# power.net
KiCad netlist of a schematic drawn in Altium Designer
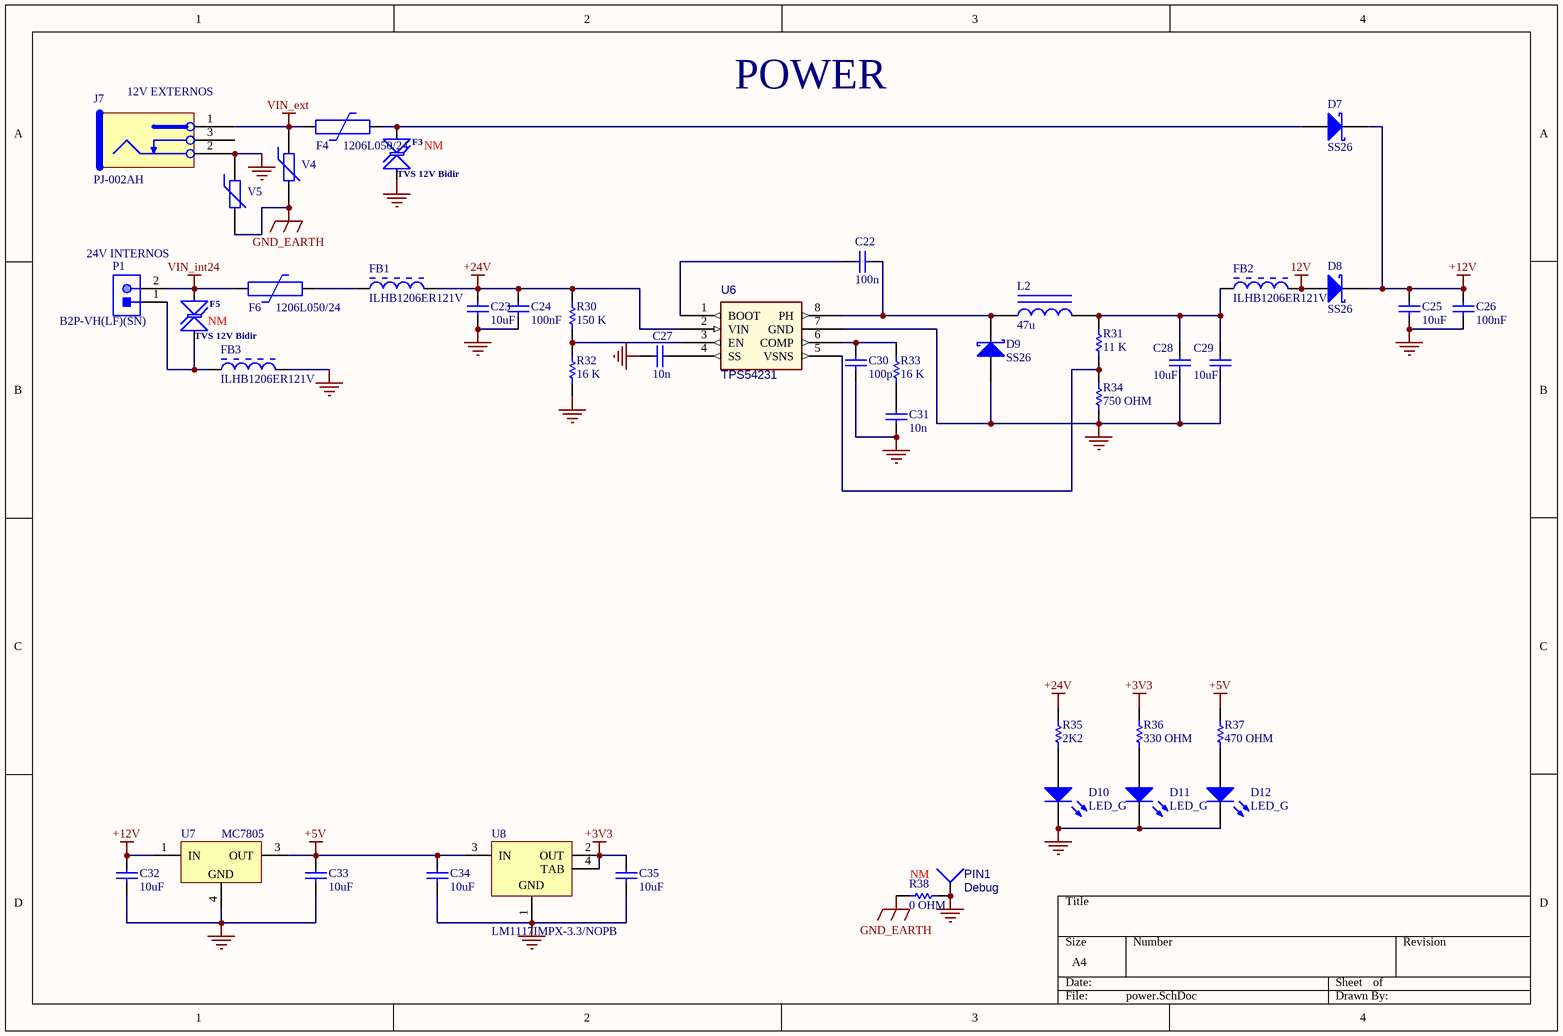
[diagram p0: power.SchDoc]

(export (version "E")
  (design (tool "Eeschema 10.0.6"))
  (components
    (comp (ref "C22")
      (value "100n")
      (footprint "0603")
      (description "Capacitor")
      (fields (field (name "PUBLISHER") "Altium Limited"))
      (libsource (lib "sallen") (part "cond"))
    )
    (comp (ref "C23")
      (value "10uF")
      (footprint "1206")
      (description "Capacitor")
      (fields (field (name "PUBLISHER") "Altium Limited"))
      (libsource (lib "sallen") (part "cond"))
    )
    (comp (ref "C24")
      (value "100nF")
      (footprint "0805")
      (description "Capacitor")
      (fields (field (name "PUBLISHER") "Altium Limited"))
      (libsource (lib "sallen") (part "cond"))
    )
    (comp (ref "C25")
      (value "10uF")
      (footprint "1206")
      (description "Capacitor")
      (fields (field (name "PUBLISHER") "Altium Limited"))
      (libsource (lib "sallen") (part "cond"))
    )
    (comp (ref "C26")
      (value "100nF")
      (footprint "0805")
      (description "Capacitor")
      (fields (field (name "PUBLISHER") "Altium Limited"))
      (libsource (lib "sallen") (part "cond"))
    )
    (comp (ref "C27")
      (value "10n")
      (footprint "0603")
      (description "Capacitor")
      (fields (field (name "PUBLISHER") "Altium Limited"))
      (libsource (lib "sallen") (part "cond"))
    )
    (comp (ref "C28")
      (value "10uF")
      (footprint "1206")
      (description "Capacitor")
      (fields (field (name "PUBLISHER") "Altium Limited"))
      (libsource (lib "sallen") (part "cond"))
    )
    (comp (ref "C29")
      (value "10uF")
      (footprint "1206")
      (description "Capacitor")
      (fields (field (name "PUBLISHER") "Altium Limited"))
      (libsource (lib "sallen") (part "cond"))
    )
    (comp (ref "C30")
      (value "100p")
      (footprint "0603")
      (description "Capacitor")
      (fields (field (name "PUBLISHER") "Altium Limited"))
      (libsource (lib "sallen") (part "cond"))
    )
    (comp (ref "C31")
      (value "10n")
      (footprint "0603")
      (description "Capacitor")
      (fields (field (name "PUBLISHER") "Altium Limited"))
      (libsource (lib "sallen") (part "cond"))
    )
    (comp (ref "C32")
      (value "10uF")
      (footprint "1206")
      (description "Capacitor")
      (fields (field (name "PUBLISHER") "Altium Limited"))
      (libsource (lib "sallen") (part "cond"))
    )
    (comp (ref "C33")
      (value "10uF")
      (footprint "0805")
      (description "Capacitor")
      (fields (field (name "PUBLISHER") "Altium Limited"))
      (libsource (lib "sallen") (part "cond"))
    )
    (comp (ref "C34")
      (value "10uF")
      (footprint "1206")
      (description "Capacitor")
      (fields (field (name "PUBLISHER") "Altium Limited"))
      (libsource (lib "sallen") (part "cond"))
    )
    (comp (ref "C35")
      (value "10uF")
      (footprint "0805")
      (description "Capacitor")
      (fields (field (name "PUBLISHER") "Altium Limited"))
      (libsource (lib "sallen") (part "cond"))
    )
    (comp (ref "D7")
      (value "SS26")
      (footprint "SMB")
      (description "Schottky Diode")
      (fields (field (name "PUBLISHER") "Altium Limited"))
      (libsource (lib "sallen") (part "D Schottky"))
    )
    (comp (ref "D8")
      (value "SS26")
      (footprint "SMB")
      (description "Schottky Diode")
      (fields (field (name "PUBLISHER") "Altium Limited"))
      (libsource (lib "sallen") (part "D Schottky"))
    )
    (comp (ref "D9")
      (value "SS26")
      (footprint "SMB")
      (description "Schottky Diode")
      (fields (field (name "PUBLISHER") "Altium Limited"))
      (libsource (lib "sallen") (part "D Schottky"))
    )
    (comp (ref "D10")
      (value "LED_G")
      (footprint "LED0603G")
      (description "Typical RED, GREEN, YELLOW, AMBER GaAs LED")
      (fields (field (name "PUBLISHER") "Altium Limited"))
      (libsource (lib "sallen") (part "diodo_led"))
    )
    (comp (ref "D11")
      (value "LED_G")
      (footprint "LED0603G")
      (description "Typical RED, GREEN, YELLOW, AMBER GaAs LED")
      (fields (field (name "PUBLISHER") "Altium Limited"))
      (libsource (lib "sallen") (part "diodo_led"))
    )
    (comp (ref "D12")
      (value "LED_G")
      (footprint "LED0603G")
      (description "Typical RED, GREEN, YELLOW, AMBER GaAs LED")
      (fields (field (name "PUBLISHER") "Altium Limited"))
      (libsource (lib "sallen") (part "diodo_led"))
    )
    (comp (ref "F3")
      (value "TVS 12V Bidir")
      (footprint "DO-214AA")
      (description "TVS 12V 600W Bidir SMD")
      (libsource (lib "HSDS_2.0") (part "SMBJ12CA"))
    )
    (comp (ref "F4")
      (value "1206L050/24")
      (footprint "POLYFUSE_1206L")
      (libsource (lib "dpm_semiconductores") (part "POLYFUSE_1206L050/24"))
    )
    (comp (ref "F5")
      (value "TVS 12V Bidir")
      (footprint "DO-214AA")
      (description "TVS 12V 600W Bidir SMD")
      (libsource (lib "HSDS_2.0") (part "SMBJ12CA"))
    )
    (comp (ref "F6")
      (value "1206L050/24")
      (footprint "POLYFUSE_1206L")
      (libsource (lib "dpm_semiconductores") (part "POLYFUSE_1206L050/24"))
    )
    (comp (ref "FB1") (value "ILHB1206ER121V") (footprint "1206") (libsource (lib "sallen") (part "FERRITA")))
    (comp (ref "FB2") (value "ILHB1206ER121V") (footprint "1206") (libsource (lib "sallen") (part "FERRITA")))
    (comp (ref "FB3") (value "ILHB1206ER121V") (footprint "1206") (libsource (lib "sallen") (part "FERRITA")))
    (comp (ref "J7")
      (value "PJ-002AH")
      (footprint "POWER_JACK_5.5_2.1MM_NS_v1.1")
      (description "CONN PWR JACK 2.1X5.5MM HIGH CUR")
      (fields
        (field (name "MANUFACTURER") "CUI Inc")
        (field (name ".CHECKED PCB") "MM")
        (field (name ".CHECKED SCH") "MM")
        (field (name ".CREATOR") "MM")
      )
      (libsource (lib "OpenRex_V1I1") (part "PJ-002AH_v1.1"))
    )
    (comp (ref "L2")
      (value "47u")
      (footprint "SRU1048-470Y")
      (description "SRU1048-470Y")
      (libsource (lib "dpm_pasivos") (part "SRU1048-470Y"))
    )
    (comp (ref "P1")
      (value "B2P-VH(LF)(SN)")
      (footprint "JST-B2P-VH(LF)(SN)_V")
      (fields (field (name "TOLERANCE") "5%"))
      (libsource (lib "sallen") (part "B2P-VH(LF)(SN)"))
    )
    (comp (ref "PIN1")
      (value "Debug")
      (description "PIN DE NET PUNTUAL /Pin Strip")
      (libsource (lib "LMB_Board") (part "Pin_Debug"))
    )
    (comp (ref "R30")
      (value "150 K")
      (footprint "R0603")
      (description "Resistor")
      (fields (field (name "PUBLISHER") "Altium Limited"))
      (libsource (lib "sallen") (part "res1"))
    )
    (comp (ref "R31")
      (value "11 K")
      (footprint "R0603")
      (description "Resistor")
      (fields (field (name "PUBLISHER") "Altium Limited"))
      (libsource (lib "sallen") (part "res1"))
    )
    (comp (ref "R32")
      (value "16 K")
      (footprint "R0603")
      (description "Resistor")
      (fields (field (name "PUBLISHER") "Altium Limited"))
      (libsource (lib "sallen") (part "res1"))
    )
    (comp (ref "R33")
      (value "16 K")
      (footprint "R0603")
      (description "Resistor")
      (fields (field (name "PUBLISHER") "Altium Limited"))
      (libsource (lib "sallen") (part "res1"))
    )
    (comp (ref "R34")
      (value "750 OHM")
      (footprint "R0603")
      (description "Resistor")
      (fields (field (name "PUBLISHER") "Altium Limited"))
      (libsource (lib "sallen") (part "res1"))
    )
    (comp (ref "R35")
      (value "2K2")
      (footprint "R0603")
      (description "Resistor")
      (fields (field (name "PUBLISHER") "Altium Limited"))
      (libsource (lib "sallen") (part "res1"))
    )
    (comp (ref "R36")
      (value "330 OHM")
      (footprint "R0603")
      (description "Resistor")
      (fields (field (name "PUBLISHER") "Altium Limited"))
      (libsource (lib "sallen") (part "res1"))
    )
    (comp (ref "R37")
      (value "470 OHM")
      (footprint "R0603")
      (description "Resistor")
      (fields (field (name "PUBLISHER") "Altium Limited"))
      (libsource (lib "sallen") (part "res1"))
    )
    (comp (ref "R38")
      (value "0 OHM")
      (footprint "R1206")
      (description "Resistor")
      (fields (field (name "PUBLISHER") "Altium Limited"))
      (libsource (lib "sallen") (part "res1"))
    )
    (comp (ref "U6")
      (value "TPS54231")
      (description "2A, 28V INPUT, STEP DOWN SWIFT™ DC/DC CONVERTER WITH ECO-MODE")
      (fields (field (name "PART NUMBER") "TEXAS TPS54231D") (field (name "PROVIDER") "ISEE"))
      (libsource (lib "LMB_Board") (part "TPS54231"))
    )
    (comp (ref "U7") (value "MC7805") (footprint "D2PAK") (libsource (lib "sallen") (part "MC7805")))
    (comp (ref "U8")
      (value "LM1117IMPX-3.3/NOPB")
      (footprint "SOT223_")
      (description "800mA Low-Dropout Linear Regulator, 4-pin SOT-223, Pb-Free")
      (fields (field (name "MANUFACTURER") "National Semiconductor"))
      (libsource (lib "sallen") (part "LM1117IMPX-3.3/NOPB"))
    )
    (comp (ref "V4")
      (value "VC080526C580")
      (footprint "VC080526C580")
      (description "Varistor (Voltage-Sensitive Resistor)")
      (libsource (lib "dpm_pasivos") (part "VC080526C580"))
    )
    (comp (ref "V5")
      (value "VC080526C580")
      (footprint "VC080526C580")
      (description "Varistor (Voltage-Sensitive Resistor)")
      (libsource (lib "dpm_pasivos") (part "VC080526C580"))
    )
  )
  (nets
    (net (code "1") (name "+3V3") (class "Default")
      (node (ref "C35") (pin "2") (pinfunction "2_2") (pintype "passive"))
      (node (ref "R36") (pin "2") (pinfunction "2_2") (pintype "passive"))
      (node (ref "U8") (pin "2") (pinfunction "OUT_2") (pintype "power_in"))
      (node (ref "U8") (pin "4") (pinfunction "TAB_4") (pintype "power_in"))
    )
    (net (code "2") (name "+5V") (class "Default")
      (node (ref "C33") (pin "2") (pinfunction "2_2") (pintype "passive"))
      (node (ref "C34") (pin "2") (pinfunction "2_2") (pintype "passive"))
      (node (ref "R37") (pin "2") (pinfunction "2_2") (pintype "passive"))
      (node (ref "U7") (pin "3") (pinfunction "OUT_3") (pintype "power_in"))
      (node (ref "U8") (pin "3") (pinfunction "IN_3") (pintype "power_in"))
    )
    (net (code "3") (name "+12V") (class "Default")
      (node (ref "C25") (pin "1") (pinfunction "1_1") (pintype "passive"))
      (node (ref "C26") (pin "2") (pinfunction "2_2") (pintype "passive"))
      (node (ref "C32") (pin "2") (pinfunction "2_2") (pintype "passive"))
      (node (ref "D7") (pin "2") (pinfunction "K_2") (pintype "passive"))
      (node (ref "D8") (pin "2") (pinfunction "K_2") (pintype "passive"))
      (node (ref "U7") (pin "1") (pinfunction "IN_1") (pintype "power_in"))
    )
    (net (code "4") (name "+24V") (class "Default")
      (node (ref "C23") (pin "2") (pinfunction "2_2") (pintype "passive"))
      (node (ref "C24") (pin "2") (pinfunction "2_2") (pintype "passive"))
      (node (ref "FB1") (pin "2") (pinfunction "2_2") (pintype "passive"))
      (node (ref "R30") (pin "2") (pinfunction "2_2") (pintype "passive"))
      (node (ref "R35") (pin "2") (pinfunction "2_2") (pintype "passive"))
      (node (ref "U6") (pin "2") (pinfunction "VIN_2") (pintype "input"))
    )
    (net (code "5") (name "12V") (class "Default")
      (node (ref "D8") (pin "1") (pinfunction "A_1") (pintype "passive"))
      (node (ref "FB2") (pin "2") (pinfunction "2_2") (pintype "passive"))
    )
    (net (code "6") (name "GND") (class "Default")
      (node (ref "C23") (pin "1") (pinfunction "1_1") (pintype "passive"))
      (node (ref "C24") (pin "1") (pinfunction "1_1") (pintype "passive"))
      (node (ref "C25") (pin "2") (pinfunction "2_2") (pintype "passive"))
      (node (ref "C26") (pin "1") (pinfunction "1_1") (pintype "passive"))
      (node (ref "C27") (pin "2") (pinfunction "2_2") (pintype "passive"))
      (node (ref "C28") (pin "1") (pinfunction "1_1") (pintype "passive"))
      (node (ref "C29") (pin "1") (pinfunction "1_1") (pintype "passive"))
      (node (ref "C30") (pin "1") (pinfunction "1_1") (pintype "passive"))
      (node (ref "C31") (pin "1") (pinfunction "1_1") (pintype "passive"))
      (node (ref "C32") (pin "1") (pinfunction "1_1") (pintype "passive"))
      (node (ref "C33") (pin "1") (pinfunction "1_1") (pintype "passive"))
      (node (ref "C34") (pin "1") (pinfunction "1_1") (pintype "passive"))
      (node (ref "C35") (pin "1") (pinfunction "1_1") (pintype "passive"))
      (node (ref "D10") (pin "2") (pinfunction "K_2") (pintype "passive"))
      (node (ref "D11") (pin "2") (pinfunction "K_2") (pintype "passive"))
      (node (ref "D12") (pin "2") (pinfunction "K_2") (pintype "passive"))
      (node (ref "D9") (pin "1") (pinfunction "A_1") (pintype "passive"))
      (node (ref "F3") (pin "1") (pinfunction "A_1") (pintype "passive"))
      (node (ref "FB3") (pin "2") (pinfunction "2_2") (pintype "passive"))
      (node (ref "J7") (pin "2") (pinfunction "2_2") (pintype "passive"))
      (node (ref "PIN1") (pin "1") (pinfunction "1_1") (pintype "passive"))
      (node (ref "R32") (pin "1") (pinfunction "1_1") (pintype "passive"))
      (node (ref "R34") (pin "1") (pinfunction "1_1") (pintype "passive"))
      (node (ref "R38") (pin "2") (pinfunction "2_2") (pintype "passive"))
      (node (ref "U6") (pin "7") (pinfunction "GND_7") (pintype "passive"))
      (node (ref "U7") (pin "4") (pinfunction "GND_4") (pintype "power_in"))
      (node (ref "U8") (pin "1") (pinfunction "GND_1") (pintype "power_in"))
      (node (ref "V5") (pin "1") (pinfunction "1_1") (pintype "passive"))
    )
    (net (code "7") (name "GND_EARTH") (class "Default")
      (node (ref "R38") (pin "1") (pinfunction "1_1") (pintype "passive"))
      (node (ref "V4") (pin "2") (pinfunction "2_2") (pintype "passive"))
      (node (ref "V5") (pin "2") (pinfunction "2_2") (pintype "passive"))
    )
    (net (code "8") (name "Net-(C28-Pad2)") (class "Default")
      (node (ref "C28") (pin "2") (pinfunction "2_2") (pintype "passive"))
      (node (ref "C29") (pin "2") (pinfunction "2_2") (pintype "passive"))
      (node (ref "FB2") (pin "1") (pinfunction "1_1") (pintype "passive"))
      (node (ref "L2") (pin "2") (pinfunction "2_2") (pintype "passive"))
      (node (ref "R31") (pin "2") (pinfunction "2_2") (pintype "passive"))
    )
    (net (code "9") (name "Net-(C31-Pad2)") (class "Default")
      (node (ref "C31") (pin "2") (pinfunction "2_2") (pintype "passive"))
      (node (ref "R33") (pin "1") (pinfunction "1_1") (pintype "passive"))
    )
    (net (code "10") (name "Net-(D7-A)") (class "Default")
      (node (ref "D7") (pin "1") (pinfunction "A_1") (pintype "passive"))
      (node (ref "F3") (pin "2") (pinfunction "K_2") (pintype "passive"))
      (node (ref "F4") (pin "2") (pinfunction "2_2") (pintype "passive"))
    )
    (net (code "11") (name "Net-(D9-K)") (class "Default")
      (node (ref "C22") (pin "2") (pinfunction "2_2") (pintype "passive"))
      (node (ref "D9") (pin "2") (pinfunction "K_2") (pintype "passive"))
      (node (ref "L2") (pin "1") (pinfunction "1_1") (pintype "passive"))
      (node (ref "U6") (pin "8") (pinfunction "PH_8") (pintype "output"))
    )
    (net (code "12") (name "Net-(D10-A)") (class "Default")
      (node (ref "D10") (pin "1") (pinfunction "A_1") (pintype "passive"))
      (node (ref "R35") (pin "1") (pinfunction "1_1") (pintype "passive"))
    )
    (net (code "13") (name "Net-(D11-A)") (class "Default")
      (node (ref "D11") (pin "1") (pinfunction "A_1") (pintype "passive"))
      (node (ref "R36") (pin "1") (pinfunction "1_1") (pintype "passive"))
    )
    (net (code "14") (name "Net-(D12-A)") (class "Default")
      (node (ref "D12") (pin "1") (pinfunction "A_1") (pintype "passive"))
      (node (ref "R37") (pin "1") (pinfunction "1_1") (pintype "passive"))
    )
    (net (code "15") (name "Net-(F5-A)") (class "Default")
      (node (ref "F5") (pin "1") (pinfunction "A_1") (pintype "passive"))
      (node (ref "FB3") (pin "1") (pinfunction "1_1") (pintype "passive"))
      (node (ref "P1") (pin "1") (pinfunction "1_1") (pintype "passive"))
    )
    (net (code "16") (name "Net-(F6-Pad2)") (class "Default")
      (node (ref "F6") (pin "2") (pinfunction "2_2") (pintype "passive"))
      (node (ref "FB1") (pin "1") (pinfunction "1_1") (pintype "passive"))
    )
    (net (code "17") (name "Net-(U6-BOOT)") (class "Default")
      (node (ref "C22") (pin "1") (pinfunction "1_1") (pintype "passive"))
      (node (ref "U6") (pin "1") (pinfunction "BOOT_1") (pintype "output"))
    )
    (net (code "18") (name "Net-(U6-COMP)") (class "Default")
      (node (ref "C30") (pin "2") (pinfunction "2_2") (pintype "passive"))
      (node (ref "R33") (pin "2") (pinfunction "2_2") (pintype "passive"))
      (node (ref "U6") (pin "6") (pinfunction "COMP_6") (pintype "output"))
    )
    (net (code "19") (name "Net-(U6-EN)") (class "Default")
      (node (ref "R30") (pin "1") (pinfunction "1_1") (pintype "passive"))
      (node (ref "R32") (pin "2") (pinfunction "2_2") (pintype "passive"))
      (node (ref "U6") (pin "3") (pinfunction "EN_3") (pintype "output"))
    )
    (net (code "20") (name "Net-(U6-SS)") (class "Default")
      (node (ref "C27") (pin "1") (pinfunction "1_1") (pintype "passive"))
      (node (ref "U6") (pin "4") (pinfunction "SS_4") (pintype "output"))
    )
    (net (code "21") (name "Net-(U6-VSNS)") (class "Default")
      (node (ref "R31") (pin "1") (pinfunction "1_1") (pintype "passive"))
      (node (ref "R34") (pin "2") (pinfunction "2_2") (pintype "passive"))
      (node (ref "U6") (pin "5") (pinfunction "VSNS_5") (pintype "output"))
    )
    (net (code "22") (name "VIN_ext") (class "Default")
      (node (ref "F4") (pin "1") (pinfunction "1_1") (pintype "passive"))
      (node (ref "J7") (pin "1") (pinfunction "1_1") (pintype "passive"))
      (node (ref "V4") (pin "1") (pinfunction "1_1") (pintype "passive"))
    )
    (net (code "23") (name "VIN_int24") (class "Default")
      (node (ref "F5") (pin "2") (pinfunction "K_2") (pintype "passive"))
      (node (ref "F6") (pin "1") (pinfunction "1_1") (pintype "passive"))
      (node (ref "P1") (pin "2") (pinfunction "2_2") (pintype "passive"))
    )
    (net (code "24") (name "unconnected-(J7-Pad3)") (class "Default")
      (node (ref "J7") (pin "3") (pinfunction "3_3") (pintype "passive"))
    )
  )
)
